# AIRZAI_NFC_READER_FLEX.net
KiCad netlist of a schematic drawn in Altium Designer
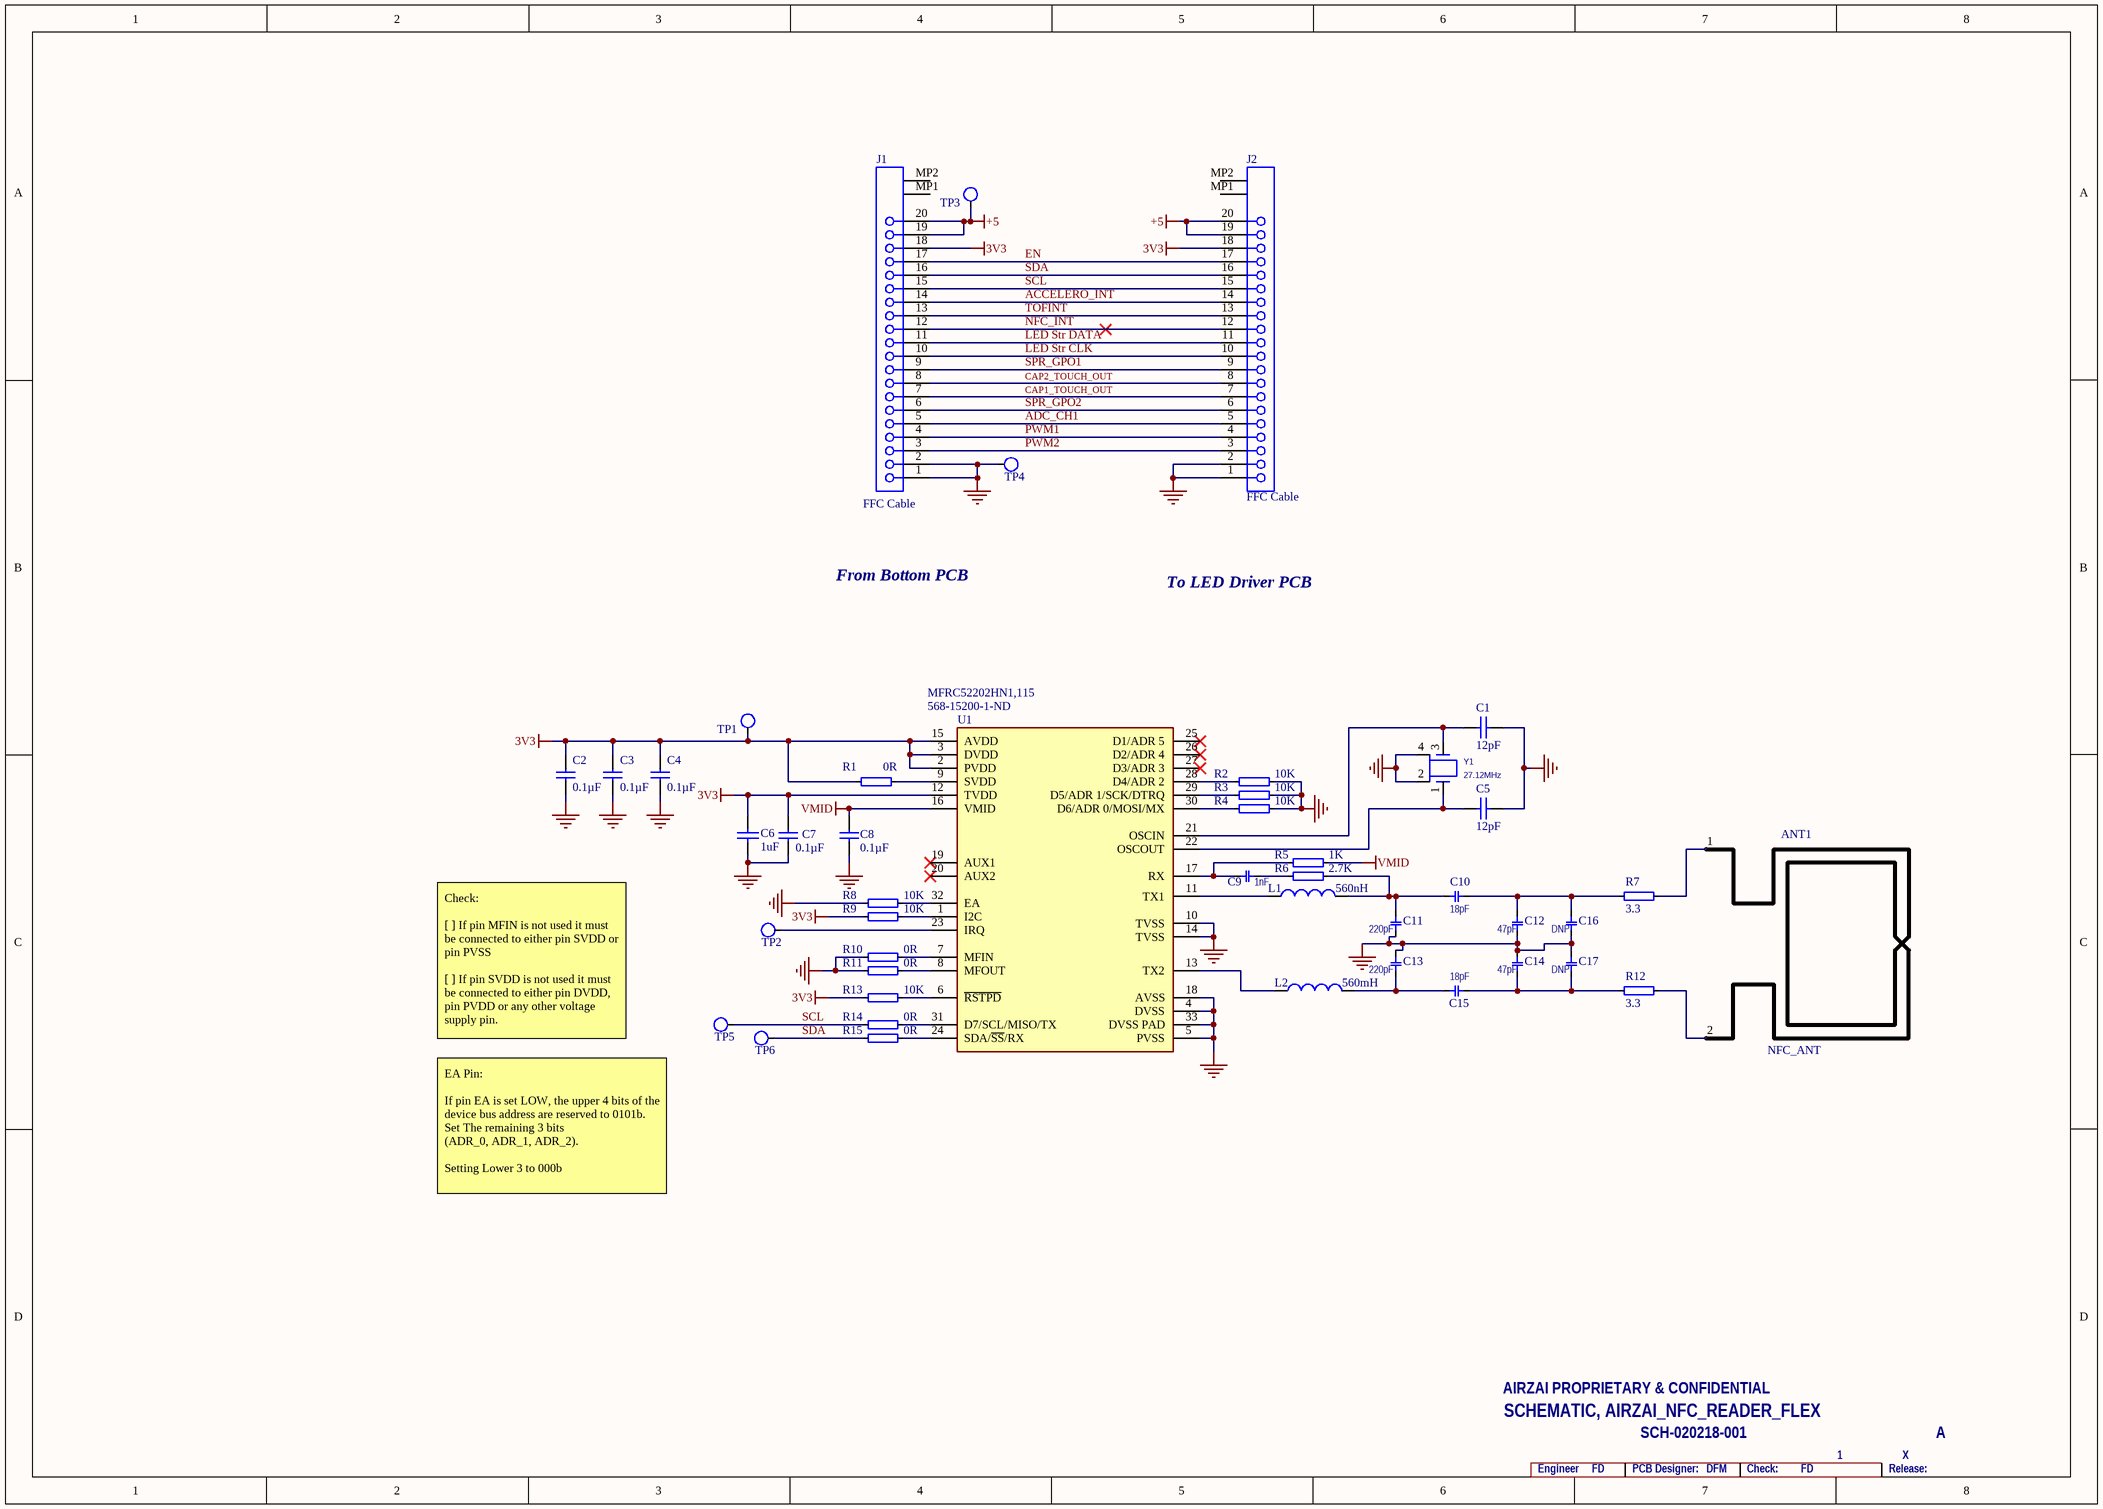
[diagram p0: AIRZAI_NFC_READER_FLEX.SchDoc]

(export (version "E")
  (design (tool "Eeschema 10.0.6"))
  (components
    (comp (ref "ANT1")
      (value "NFC_ANT")
      (footprint "ANTENNA-NFC-60MMX30MM")
      (libsource (lib "AIRZAI_LED_SENSE_FLEX_REVA") (part "NFC_ANT"))
    )
    (comp (ref "C1")
      (value "12pF")
      (footprint "0402CAP")
      (description "CAP CER 12PF 50V C0G/NP0 0402")
      (fields
        (field (name "MANUFACTURER") "KEMET")
        (field (name "MANUFACTURER PART NUMBER") "C0402C120J5GACTU")
      )
      (libsource (lib "AIRZAI_LED_SENSE_FLEX_REVA") (part "CAP"))
    )
    (comp (ref "C2")
      (value "0.1µF")
      (footprint "0402CAP")
      (description "Capacitor, X7R, ±10%")
      (fields (field (name "MANUFACTURER") "TDK") (field (name "MANUFACTURER PART NUMBER") "C1005X7R1C104K"))
      (libsource (lib "Nordic Passive DB") (part "CAP"))
    )
    (comp (ref "C3")
      (value "0.1µF")
      (footprint "0402CAP")
      (description "Capacitor, X7R, ±10%")
      (fields (field (name "MANUFACTURER") "TDK") (field (name "MANUFACTURER PART NUMBER") "C1005X7R1C104K"))
      (libsource (lib "Nordic Passive DB") (part "CAP"))
    )
    (comp (ref "C4")
      (value "0.1µF")
      (footprint "0402CAP")
      (description "Capacitor, X7R, ±10%")
      (fields (field (name "MANUFACTURER") "TDK") (field (name "MANUFACTURER PART NUMBER") "C1005X7R1C104K"))
      (libsource (lib "Nordic Passive DB") (part "CAP"))
    )
    (comp (ref "C5")
      (value "12pF")
      (footprint "0402CAP")
      (description "CAP CER 12PF 50V C0G/NP0 0402")
      (fields
        (field (name "MANUFACTURER") "KEMET")
        (field (name "MANUFACTURER PART NUMBER") "C0402C120J5GACTU")
      )
      (libsource (lib "AIRZAI_LED_SENSE_FLEX_REVA") (part "CAP"))
    )
    (comp (ref "C6")
      (value "1uF")
      (footprint "CAPC0402(1005)60_M")
      (description "CAP 1uF 16V ±10% 0402 (1005 Metric) Thickness 0.6mm SMD")
      (fields
        (field (name "MANUFACTURER") "Taiyo Yuden")
        (field (name "MANUFACTURER PART NUMBER") "EMK105BJ105KV-F")
      )
      (libsource (lib "AIRZAI_LED_SENSE_FLEX_REVA") (part "CAP"))
    )
    (comp (ref "C7")
      (value "0.1µF")
      (footprint "0402CAP")
      (description "Capacitor, X7R, ±10%")
      (fields (field (name "MANUFACTURER") "TDK") (field (name "MANUFACTURER PART NUMBER") "C1005X7R1C104K"))
      (libsource (lib "Nordic Passive DB") (part "CAP"))
    )
    (comp (ref "C8")
      (value "0.1µF")
      (footprint "0402CAP")
      (description "Capacitor, X7R, ±10%")
      (fields (field (name "MANUFACTURER") "TDK") (field (name "MANUFACTURER PART NUMBER") "C1005X7R1C104K"))
      (libsource (lib "Nordic Passive DB") (part "CAP"))
    )
    (comp (ref "C9")
      (value "1nF")
      (footprint "0402CAP")
      (description "CAP CER 1000PF 50V C0G/NP0 0402")
      (fields
        (field (name "MANUFACTURER") "Murata")
        (field (name "MANUFACTURER PART NUMBER") "GRM1555C1H102FA01D")
      )
      (libsource (lib "LID2131_PN7462AU V2") (part "56p"))
    )
    (comp (ref "C10")
      (value "18pF")
      (footprint "0402CAP")
      (description "CAP CER 18PF 50V NP0 0402")
      (fields
        (field (name "MANUFACTURER") "Kyocera AVX")
        (field (name "MANUFACTURER PART NUMBER") "04025U180FAT2A")
      )
      (libsource (lib "LID2131_PN7462AU V2") (part "56p"))
    )
    (comp (ref "C11")
      (value "220pF")
      (footprint "0402CAP")
      (description "CAP CER 220PF 50V NPO 0402")
      (fields
        (field (name "MANUFACTURER") "Yageo")
        (field (name "MANUFACTURER PART NUMBER") "CC0402FRNPO9BN221")
      )
      (libsource (lib "LID2131_PN7462AU V2") (part "56p"))
    )
    (comp (ref "C12")
      (value "47pF")
      (footprint "0402CAP")
      (description "CAP CER 47PF 50V C0G/NP0 0402")
      (fields
        (field (name "MANUFACTURER") "Murata")
        (field (name "MANUFACTURER PART NUMBER") "GJM1555C1H470FB01D")
      )
      (libsource (lib "LID2131_PN7462AU V2") (part "56p"))
    )
    (comp (ref "C13")
      (value "220pF")
      (footprint "0402CAP")
      (description "CAP CER 220PF 50V NPO 0402")
      (fields
        (field (name "MANUFACTURER") "Yageo")
        (field (name "MANUFACTURER PART NUMBER") "CC0402FRNPO9BN221")
      )
      (libsource (lib "LID2131_PN7462AU V2") (part "56p"))
    )
    (comp (ref "C14")
      (value "47pF")
      (footprint "0402CAP")
      (description "CAP CER 47PF 50V C0G/NP0 0402")
      (fields
        (field (name "MANUFACTURER") "Murata")
        (field (name "MANUFACTURER PART NUMBER") "GJM1555C1H470FB01D")
      )
      (libsource (lib "LID2131_PN7462AU V2") (part "56p"))
    )
    (comp (ref "C15")
      (value "18pF")
      (footprint "0402CAP")
      (description "CAP CER 18PF 50V NP0 0402")
      (fields
        (field (name "MANUFACTURER") "Kyocera AVX")
        (field (name "MANUFACTURER PART NUMBER") "04025U180FAT2A")
      )
      (libsource (lib "LID2131_PN7462AU V2") (part "56p"))
    )
    (comp (ref "C16")
      (value "DNP")
      (footprint "0402CAP")
      (libsource (lib "LID2131_PN7462AU V2") (part "56p"))
    )
    (comp (ref "C17")
      (value "DNP")
      (footprint "0402CAP")
      (libsource (lib "LID2131_PN7462AU V2") (part "56p"))
    )
    (comp (ref "J1")
      (value "FFC Cable")
      (footprint "FFC_Pads_MBD")
      (description "Cable")
      (libsource (lib "AIRZAI_LID_BD_REVA") (part "XF2M-2015-1A-R100"))
    )
    (comp (ref "J2")
      (value "FFC Cable")
      (footprint "FFC_Pads_LID")
      (description "Cable")
      (libsource (lib "AIRZAI_LID_BD_REVA") (part "XF2M-2015-1A-R100"))
    )
    (comp (ref "L1")
      (value "560nH")
      (footprint "0603CAP")
      (description "FIXED IND 560NH 100MA 1.05 OHM")
      (fields
        (field (name "MANUFACTURER") "TDK")
        (field (name "MANUFACTURER PART NUMBER") "MLF1608DR56JTD25")
      )
      (libsource (lib "Miscellaneous Devices") (part "Inductor"))
    )
    (comp (ref "L2")
      (value "560mH")
      (footprint "0603CAP")
      (description "FIXED IND 560NH 100MA 1.05 OHM")
      (fields
        (field (name "MANUFACTURER") "TDK")
        (field (name "MANUFACTURER PART NUMBER") "MLF1608DR56JTD25")
      )
      (libsource (lib "Miscellaneous Devices") (part "Inductor"))
    )
    (comp (ref "R1")
      (value "0R")
      (footprint "0402")
      (description "Resistor, ±1%, 0.063W")
      (fields
        (field (name "MANUFACTURER") "Panasonic")
        (field (name "MANUFACTURER PART NUMBER") "ERJ-2GE0R00X")
      )
      (libsource (lib "Nordic Passive DB") (part "RES_1"))
    )
    (comp (ref "R2")
      (value "10K")
      (footprint "0402")
      (description "Resistor 10K, ±1%, 0.063W")
      (fields
        (field (name "MANUFACTURER") "Vishay Dale")
        (field (name "MANUFACTURER PART NUMBER") "CRCW040210K0JNED")
      )
      (libsource (lib "Nordic Passive DB") (part "RES_1"))
    )
    (comp (ref "R3")
      (value "10K")
      (footprint "0402")
      (description "Resistor 10K, ±1%, 0.063W")
      (fields
        (field (name "MANUFACTURER") "Vishay Dale")
        (field (name "MANUFACTURER PART NUMBER") "CRCW040210K0JNED")
      )
      (libsource (lib "Nordic Passive DB") (part "RES_1"))
    )
    (comp (ref "R4")
      (value "10K")
      (footprint "0402")
      (description "Resistor 10K, ±1%, 0.063W")
      (fields
        (field (name "MANUFACTURER") "Vishay Dale")
        (field (name "MANUFACTURER PART NUMBER") "CRCW040210K0JNED")
      )
      (libsource (lib "Nordic Passive DB") (part "RES_1"))
    )
    (comp (ref "R5")
      (value "1K")
      (footprint "0402")
      (description "RES SMD 1K OHM 1% 1/16W 0402")
      (fields
        (field (name "MANUFACTURER") "Yageo")
        (field (name "MANUFACTURER PART NUMBER") "RC0402FR-071KL")
      )
      (libsource (lib "Nordic Passive DB") (part "RES_1"))
    )
    (comp (ref "R6")
      (value "2.7K")
      (footprint "0402")
      (description "RES SMD 2.7K OHM 1% 1/16W 0402")
      (fields
        (field (name "MANUFACTURER") "Yageo Phycomp")
        (field (name "MANUFACTURER PART NUMBER") "RC0402FR-072K7L")
      )
      (libsource (lib "Nordic Passive DB") (part "RES_1"))
    )
    (comp (ref "R7")
      (value "3.3")
      (footprint "0603")
      (description "RES SMD 3.3 OHM 1% 1/10W 0603")
      (fields
        (field (name "MANUFACTURER") "Yageo")
        (field (name "MANUFACTURER PART NUMBER") "AC0603FR-073R3L")
      )
      (libsource (lib "Nordic Passive DB") (part "RES_1"))
    )
    (comp (ref "R8")
      (value "10K")
      (footprint "0402")
      (description "Resistor 10K, ±1%, 0.063W")
      (fields
        (field (name "MANUFACTURER") "Vishay Dale")
        (field (name "MANUFACTURER PART NUMBER") "CRCW040210K0JNED")
      )
      (libsource (lib "Nordic Passive DB") (part "RES_1"))
    )
    (comp (ref "R9")
      (value "10K")
      (footprint "0402")
      (description "Resistor 10K, ±1%, 0.063W")
      (fields
        (field (name "MANUFACTURER") "Vishay Dale")
        (field (name "MANUFACTURER PART NUMBER") "CRCW040210K0JNED")
      )
      (libsource (lib "Nordic Passive DB") (part "RES_1"))
    )
    (comp (ref "R10")
      (value "0R")
      (footprint "0402")
      (description "Resistor, ±1%, 0.063W")
      (fields
        (field (name "MANUFACTURER") "Panasonic")
        (field (name "MANUFACTURER PART NUMBER") "ERJ-2GE0R00X")
      )
      (libsource (lib "Nordic Passive DB") (part "RES_1"))
    )
    (comp (ref "R11")
      (value "0R")
      (footprint "0402")
      (description "Resistor, ±1%, 0.063W")
      (fields
        (field (name "MANUFACTURER") "Panasonic")
        (field (name "MANUFACTURER PART NUMBER") "ERJ-2GE0R00X")
      )
      (libsource (lib "Nordic Passive DB") (part "RES_1"))
    )
    (comp (ref "R12")
      (value "3.3")
      (footprint "0603")
      (description "RES SMD 3.3 OHM 1% 1/10W 0603")
      (fields
        (field (name "MANUFACTURER") "Yageo")
        (field (name "MANUFACTURER PART NUMBER") "AC0603FR-073R3L")
      )
      (libsource (lib "Nordic Passive DB") (part "RES_1"))
    )
    (comp (ref "R13")
      (value "10K")
      (footprint "0402")
      (description "Resistor 10K, ±1%, 0.063W")
      (fields
        (field (name "MANUFACTURER") "Vishay Dale")
        (field (name "MANUFACTURER PART NUMBER") "CRCW040210K0JNED")
      )
      (libsource (lib "Nordic Passive DB") (part "RES_1"))
    )
    (comp (ref "R14")
      (value "0R")
      (footprint "0402")
      (description "Resistor, ±1%, 0.063W")
      (fields
        (field (name "MANUFACTURER") "Panasonic")
        (field (name "MANUFACTURER PART NUMBER") "ERJ-2GE0R00X")
      )
      (libsource (lib "Nordic Passive DB") (part "RES_1"))
    )
    (comp (ref "R15")
      (value "0R")
      (footprint "0402")
      (description "Resistor, ±1%, 0.063W")
      (fields
        (field (name "MANUFACTURER") "Panasonic")
        (field (name "MANUFACTURER PART NUMBER") "ERJ-2GE0R00X")
      )
      (libsource (lib "Nordic Passive DB") (part "RES_1"))
    )
    (comp (ref "TP1")
      (value "WIREPT")
      (footprint "TP_0.9MM")
      (libsource (lib "AIRZAI_MBD_REVB") (part "WIREPT"))
    )
    (comp (ref "TP2")
      (value "WIREPT")
      (footprint "TP_0.9MM")
      (libsource (lib "AIRZAI_MBD_REVB") (part "WIREPT"))
    )
    (comp (ref "TP3")
      (value "WIREPT")
      (footprint "TP_0.9MM")
      (libsource (lib "AIRZAI_MBD_REVB") (part "WIREPT"))
    )
    (comp (ref "TP4")
      (value "WIREPT")
      (footprint "TP_0.9MM")
      (libsource (lib "AIRZAI_MBD_REVB") (part "WIREPT"))
    )
    (comp (ref "TP5")
      (value "WIREPT")
      (footprint "TP_0.9MM")
      (libsource (lib "AIRZAI_MBD_REVB") (part "WIREPT"))
    )
    (comp (ref "TP6")
      (value "WIREPT")
      (footprint "TP_0.9MM")
      (libsource (lib "AIRZAI_MBD_REVB") (part "WIREPT"))
    )
    (comp (ref "U1")
      (value "MFRC52202HN1,115")
      (footprint "VFQFN-32-MFRC52202HN1,157")
      (description "IC RFID READER 13.56MHZ 32HVQFN")
      (fields
        (field (name "SUPPLIER PART NUMBER 1") "568-15200-1-ND")
        (field (name "MANUFACTURER") "NXP Semiconductors")
        (field (name "MANUFACTURER PART NUMBER") "MFRC52202HN1,115")
      )
      (libsource (lib "AIRZAI_LED_SENSE_FLEX_REVA") (part "MFRC52201HN1,157"))
    )
    (comp (ref "Y1")
      (value "27.12MHz")
      (footprint "XTAL_2016")
      (description "CRYSTAL 27.12MHZ 10PF SMD")
      (fields
        (field (name "MANUFACTURER") "ECS International")
        (field (name "MANUFACTURER PART NUMBER") "ECS-271.2-10-37-CKM-TR")
      )
      (libsource (lib "*") (part "ZTB_2"))
    )
  )
  (nets
    (net (code "1") (name "+5") (class "Default")
      (node (ref "J1") (pin "19") (pinfunction "19_19") (pintype "passive"))
      (node (ref "J1") (pin "20") (pinfunction "20_20") (pintype "passive"))
      (node (ref "J2") (pin "19") (pinfunction "19_19") (pintype "passive"))
      (node (ref "J2") (pin "20") (pinfunction "20_20") (pintype "passive"))
      (node (ref "TP3") (pin "1") (pinfunction "1_1") (pintype "passive"))
    )
    (net (code "2") (name "/ACCELERO_INT") (class "Default")
      (node (ref "J1") (pin "14") (pinfunction "14_14") (pintype "passive"))
      (node (ref "J2") (pin "14") (pinfunction "14_14") (pintype "passive"))
    )
    (net (code "3") (name "/ADC_CH1") (class "Default")
      (node (ref "J1") (pin "5") (pinfunction "5_5") (pintype "passive"))
      (node (ref "J2") (pin "5") (pinfunction "5_5") (pintype "passive"))
    )
    (net (code "4") (name "/CAP1_TOUCH_OUT") (class "Default")
      (node (ref "J1") (pin "7") (pinfunction "7_7") (pintype "passive"))
      (node (ref "J2") (pin "7") (pinfunction "7_7") (pintype "passive"))
    )
    (net (code "5") (name "/CAP2_TOUCH_OUT") (class "Default")
      (node (ref "J1") (pin "8") (pinfunction "8_8") (pintype "passive"))
      (node (ref "J2") (pin "8") (pinfunction "8_8") (pintype "passive"))
    )
    (net (code "6") (name "/EN") (class "Default")
      (node (ref "J1") (pin "17") (pinfunction "17_17") (pintype "passive"))
      (node (ref "J2") (pin "17") (pinfunction "17_17") (pintype "passive"))
    )
    (net (code "7") (name "/LED Str CLK") (class "Default")
      (node (ref "J1") (pin "10") (pinfunction "10_10") (pintype "passive"))
      (node (ref "J2") (pin "10") (pinfunction "10_10") (pintype "passive"))
    )
    (net (code "8") (name "/LED Str DATA") (class "Default")
      (node (ref "J1") (pin "11") (pinfunction "11_11") (pintype "passive"))
      (node (ref "J2") (pin "11") (pinfunction "11_11") (pintype "passive"))
    )
    (net (code "9") (name "/NFC_INT") (class "Default")
      (node (ref "J1") (pin "12") (pinfunction "12_12") (pintype "passive"))
      (node (ref "J2") (pin "12") (pinfunction "12_12") (pintype "passive"))
    )
    (net (code "10") (name "/PWM1") (class "Default")
      (node (ref "J1") (pin "4") (pinfunction "4_4") (pintype "passive"))
      (node (ref "J2") (pin "4") (pinfunction "4_4") (pintype "passive"))
    )
    (net (code "11") (name "/PWM2") (class "Default")
      (node (ref "J1") (pin "3") (pinfunction "3_3") (pintype "passive"))
      (node (ref "J2") (pin "3") (pinfunction "3_3") (pintype "passive"))
    )
    (net (code "12") (name "/SCL") (class "Default")
      (node (ref "J1") (pin "15") (pinfunction "15_15") (pintype "passive"))
      (node (ref "J2") (pin "15") (pinfunction "15_15") (pintype "passive"))
      (node (ref "R14") (pin "2") (pinfunction "2_2") (pintype "passive"))
      (node (ref "TP5") (pin "1") (pinfunction "1_1") (pintype "passive"))
    )
    (net (code "13") (name "/SDA") (class "Default")
      (node (ref "J1") (pin "16") (pinfunction "16_16") (pintype "passive"))
      (node (ref "J2") (pin "16") (pinfunction "16_16") (pintype "passive"))
      (node (ref "R15") (pin "2") (pinfunction "2_2") (pintype "passive"))
      (node (ref "TP6") (pin "1") (pinfunction "1_1") (pintype "passive"))
    )
    (net (code "14") (name "/SPR_GPO1") (class "Default")
      (node (ref "J1") (pin "9") (pinfunction "9_9") (pintype "passive"))
      (node (ref "J2") (pin "9") (pinfunction "9_9") (pintype "passive"))
    )
    (net (code "15") (name "/SPR_GPO2") (class "Default")
      (node (ref "J1") (pin "6") (pinfunction "6_6") (pintype "passive"))
      (node (ref "J2") (pin "6") (pinfunction "6_6") (pintype "passive"))
    )
    (net (code "16") (name "/TOFINT") (class "Default")
      (node (ref "J1") (pin "13") (pinfunction "13_13") (pintype "passive"))
      (node (ref "J2") (pin "13") (pinfunction "13_13") (pintype "passive"))
    )
    (net (code "17") (name "3V3") (class "Default")
      (node (ref "C2") (pin "1") (pinfunction "1_1") (pintype "passive"))
      (node (ref "C3") (pin "1") (pinfunction "1_1") (pintype "passive"))
      (node (ref "C4") (pin "1") (pinfunction "1_1") (pintype "passive"))
      (node (ref "C6") (pin "2") (pinfunction "2_2") (pintype "passive"))
      (node (ref "C7") (pin "1") (pinfunction "1_1") (pintype "passive"))
      (node (ref "J1") (pin "18") (pinfunction "18_18") (pintype "passive"))
      (node (ref "J2") (pin "18") (pinfunction "18_18") (pintype "passive"))
      (node (ref "R1") (pin "2") (pinfunction "2_2") (pintype "passive"))
      (node (ref "R13") (pin "2") (pinfunction "2_2") (pintype "passive"))
      (node (ref "R9") (pin "2") (pinfunction "2_2") (pintype "passive"))
      (node (ref "TP1") (pin "1") (pinfunction "1_1") (pintype "passive"))
      (node (ref "U1") (pin "12") (pinfunction "TVDD_12") (pintype "passive"))
      (node (ref "U1") (pin "15") (pinfunction "AVDD_15") (pintype "passive"))
      (node (ref "U1") (pin "2") (pinfunction "PVDD_2") (pintype "passive"))
      (node (ref "U1") (pin "3") (pinfunction "DVDD_3") (pintype "passive"))
    )
    (net (code "18") (name "GND") (class "Default")
      (node (ref "C1") (pin "1") (pinfunction "1_1") (pintype "passive"))
      (node (ref "C11") (pin "1") (pinfunction "1_1") (pintype "passive"))
      (node (ref "C12") (pin "1") (pinfunction "1_1") (pintype "passive"))
      (node (ref "C13") (pin "2") (pinfunction "2_2") (pintype "passive"))
      (node (ref "C14") (pin "2") (pinfunction "2_2") (pintype "passive"))
      (node (ref "C16") (pin "1") (pinfunction "1_1") (pintype "passive"))
      (node (ref "C17") (pin "2") (pinfunction "2_2") (pintype "passive"))
      (node (ref "C2") (pin "2") (pinfunction "2_2") (pintype "passive"))
      (node (ref "C3") (pin "2") (pinfunction "2_2") (pintype "passive"))
      (node (ref "C4") (pin "2") (pinfunction "2_2") (pintype "passive"))
      (node (ref "C5") (pin "1") (pinfunction "1_1") (pintype "passive"))
      (node (ref "C6") (pin "1") (pinfunction "1_1") (pintype "passive"))
      (node (ref "C7") (pin "2") (pinfunction "2_2") (pintype "passive"))
      (node (ref "C8") (pin "2") (pinfunction "2_2") (pintype "passive"))
      (node (ref "J1") (pin "1") (pinfunction "1_1") (pintype "passive"))
      (node (ref "J1") (pin "2") (pinfunction "2_2") (pintype "passive"))
      (node (ref "J2") (pin "1") (pinfunction "1_1") (pintype "passive"))
      (node (ref "J2") (pin "2") (pinfunction "2_2") (pintype "passive"))
      (node (ref "R10") (pin "2") (pinfunction "2_2") (pintype "passive"))
      (node (ref "R11") (pin "2") (pinfunction "2_2") (pintype "passive"))
      (node (ref "R2") (pin "1") (pinfunction "1_1") (pintype "passive"))
      (node (ref "R3") (pin "1") (pinfunction "1_1") (pintype "passive"))
      (node (ref "R4") (pin "1") (pinfunction "1_1") (pintype "passive"))
      (node (ref "R8") (pin "2") (pinfunction "2_2") (pintype "passive"))
      (node (ref "TP4") (pin "1") (pinfunction "1_1") (pintype "passive"))
      (node (ref "U1") (pin "10") (pinfunction "TVSS_10") (pintype "passive"))
      (node (ref "U1") (pin "14") (pinfunction "TVSS_14") (pintype "passive"))
      (node (ref "U1") (pin "18") (pinfunction "AVSS_18") (pintype "passive"))
      (node (ref "U1") (pin "33") (pinfunction "DVSS_PAD_33") (pintype "passive"))
      (node (ref "U1") (pin "4") (pinfunction "DVSS_4") (pintype "passive"))
      (node (ref "U1") (pin "5") (pinfunction "PVSS_5") (pintype "passive"))
      (node (ref "Y1") (pin "2") (pinfunction "2_2") (pintype "passive"))
      (node (ref "Y1") (pin "4") (pinfunction "4_4") (pintype "passive"))
    )
    (net (code "19") (name "Net-(ANT1-Pad1)") (class "Default")
      (node (ref "ANT1") (pin "1") (pinfunction "1_1") (pintype "passive"))
      (node (ref "R7") (pin "1") (pinfunction "1_1") (pintype "passive"))
    )
    (net (code "20") (name "Net-(ANT1-Pad2)") (class "Default")
      (node (ref "ANT1") (pin "2") (pinfunction "2_2") (pintype "passive"))
      (node (ref "R12") (pin "1") (pinfunction "1_1") (pintype "passive"))
    )
    (net (code "21") (name "Net-(C9-Pad1)") (class "Default")
      (node (ref "C9") (pin "1") (pinfunction "1_1") (pintype "passive"))
      (node (ref "R6") (pin "2") (pinfunction "2_2") (pintype "passive"))
    )
    (net (code "22") (name "Net-(C10-Pad1)") (class "Default")
      (node (ref "C10") (pin "1") (pinfunction "1_1") (pintype "passive"))
      (node (ref "C12") (pin "2") (pinfunction "2_2") (pintype "passive"))
      (node (ref "C16") (pin "2") (pinfunction "2_2") (pintype "passive"))
      (node (ref "R7") (pin "2") (pinfunction "2_2") (pintype "passive"))
    )
    (net (code "23") (name "Net-(C10-Pad2)") (class "Default")
      (node (ref "C10") (pin "2") (pinfunction "2_2") (pintype "passive"))
      (node (ref "C11") (pin "2") (pinfunction "2_2") (pintype "passive"))
      (node (ref "L1") (pin "2") (pinfunction "2_2") (pintype "passive"))
      (node (ref "R6") (pin "1") (pinfunction "1_1") (pintype "passive"))
    )
    (net (code "24") (name "Net-(C13-Pad1)") (class "Default")
      (node (ref "C13") (pin "1") (pinfunction "1_1") (pintype "passive"))
      (node (ref "C15") (pin "2") (pinfunction "2_2") (pintype "passive"))
      (node (ref "L2") (pin "2") (pinfunction "2_2") (pintype "passive"))
    )
    (net (code "25") (name "Net-(C14-Pad1)") (class "Default")
      (node (ref "C14") (pin "1") (pinfunction "1_1") (pintype "passive"))
      (node (ref "C15") (pin "1") (pinfunction "1_1") (pintype "passive"))
      (node (ref "C17") (pin "1") (pinfunction "1_1") (pintype "passive"))
      (node (ref "R12") (pin "2") (pinfunction "2_2") (pintype "passive"))
    )
    (net (code "26") (name "Net-(U1-D4{slash}ADR_2)") (class "Default")
      (node (ref "R2") (pin "2") (pinfunction "2_2") (pintype "passive"))
      (node (ref "U1") (pin "28") (pinfunction "D4/ADR_2_28") (pintype "passive"))
    )
    (net (code "27") (name "Net-(U1-D5{slash}ADR_1{slash}SCK{slash}DTRQ)") (class "Default")
      (node (ref "R3") (pin "2") (pinfunction "2_2") (pintype "passive"))
      (node (ref "U1") (pin "29") (pinfunction "D5/ADR_1/SCK/DTRQ_29") (pintype "passive"))
    )
    (net (code "28") (name "Net-(U1-D6{slash}ADR_0{slash}MOSI{slash}MX)") (class "Default")
      (node (ref "R4") (pin "2") (pinfunction "2_2") (pintype "passive"))
      (node (ref "U1") (pin "30") (pinfunction "D6/ADR_0/MOSI/MX_30") (pintype "passive"))
    )
    (net (code "29") (name "Net-(U1-D7{slash}SCL{slash}MISO{slash}TX)") (class "Default")
      (node (ref "R14") (pin "1") (pinfunction "1_1") (pintype "passive"))
      (node (ref "U1") (pin "31") (pinfunction "D7/SCL/MISO/TX_31") (pintype "passive"))
    )
    (net (code "30") (name "Net-(U1-EA)") (class "Default")
      (node (ref "R8") (pin "1") (pinfunction "1_1") (pintype "passive"))
      (node (ref "U1") (pin "32") (pinfunction "EA_32") (pintype "passive"))
    )
    (net (code "31") (name "Net-(U1-I2C)") (class "Default")
      (node (ref "R9") (pin "1") (pinfunction "1_1") (pintype "passive"))
      (node (ref "U1") (pin "1") (pinfunction "I2C_1") (pintype "passive"))
    )
    (net (code "32") (name "Net-(U1-IRQ)") (class "Default")
      (node (ref "TP2") (pin "1") (pinfunction "1_1") (pintype "passive"))
      (node (ref "U1") (pin "23") (pinfunction "IRQ_23") (pintype "passive"))
    )
    (net (code "33") (name "Net-(U1-MFIN)") (class "Default")
      (node (ref "R10") (pin "1") (pinfunction "1_1") (pintype "passive"))
      (node (ref "U1") (pin "7") (pinfunction "MFIN_7") (pintype "passive"))
    )
    (net (code "34") (name "Net-(U1-MFOUT)") (class "Default")
      (node (ref "R11") (pin "1") (pinfunction "1_1") (pintype "passive"))
      (node (ref "U1") (pin "8") (pinfunction "MFOUT_8") (pintype "passive"))
    )
    (net (code "35") (name "Net-(U1-OSCIN)") (class "Default")
      (node (ref "C1") (pin "2") (pinfunction "2_2") (pintype "passive"))
      (node (ref "U1") (pin "21") (pinfunction "OSCIN_21") (pintype "passive"))
      (node (ref "Y1") (pin "3") (pinfunction "3_3") (pintype "passive"))
    )
    (net (code "36") (name "Net-(U1-OSCOUT)") (class "Default")
      (node (ref "C5") (pin "2") (pinfunction "2_2") (pintype "passive"))
      (node (ref "U1") (pin "22") (pinfunction "OSCOUT_22") (pintype "passive"))
      (node (ref "Y1") (pin "1") (pinfunction "1_1") (pintype "passive"))
    )
    (net (code "37") (name "Net-(U1-RX)") (class "Default")
      (node (ref "C9") (pin "2") (pinfunction "2_2") (pintype "passive"))
      (node (ref "R5") (pin "2") (pinfunction "2_2") (pintype "passive"))
      (node (ref "U1") (pin "17") (pinfunction "RX_17") (pintype "passive"))
    )
    (net (code "38") (name "Net-(U1-SDA{slash}~{SS}{slash}RX)") (class "Default")
      (node (ref "R15") (pin "1") (pinfunction "1_1") (pintype "passive"))
      (node (ref "U1") (pin "24") (pinfunction "SDA/~{SS}/RX_24") (pintype "passive"))
    )
    (net (code "39") (name "Net-(U1-SVDD)") (class "Default")
      (node (ref "R1") (pin "1") (pinfunction "1_1") (pintype "passive"))
      (node (ref "U1") (pin "9") (pinfunction "SVDD_9") (pintype "passive"))
    )
    (net (code "40") (name "Net-(U1-TX1)") (class "Default")
      (node (ref "L1") (pin "1") (pinfunction "1_1") (pintype "passive"))
      (node (ref "U1") (pin "11") (pinfunction "TX1_11") (pintype "passive"))
    )
    (net (code "41") (name "Net-(U1-TX2)") (class "Default")
      (node (ref "L2") (pin "1") (pinfunction "1_1") (pintype "passive"))
      (node (ref "U1") (pin "13") (pinfunction "TX2_13") (pintype "passive"))
    )
    (net (code "42") (name "Net-(U1-~{RSTPD})") (class "Default")
      (node (ref "R13") (pin "1") (pinfunction "1_1") (pintype "passive"))
      (node (ref "U1") (pin "6") (pinfunction "~{RSTPD}_6") (pintype "passive"))
    )
    (net (code "43") (name "VMID") (class "Default")
      (node (ref "C8") (pin "1") (pinfunction "1_1") (pintype "passive"))
      (node (ref "R5") (pin "1") (pinfunction "1_1") (pintype "passive"))
      (node (ref "U1") (pin "16") (pinfunction "VMID_16") (pintype "passive"))
    )
    (net (code "44") (name "unconnected-(J1-PadMP1)") (class "Default")
      (node (ref "J1") (pin "MP1") (pinfunction "MP1_MP1") (pintype "passive"))
    )
    (net (code "45") (name "unconnected-(J1-PadMP2)") (class "Default")
      (node (ref "J1") (pin "MP2") (pinfunction "MP2_MP2") (pintype "passive"))
    )
    (net (code "46") (name "unconnected-(J2-PadMP1)") (class "Default")
      (node (ref "J2") (pin "MP1") (pinfunction "MP1_MP1") (pintype "passive"))
    )
    (net (code "47") (name "unconnected-(J2-PadMP2)") (class "Default")
      (node (ref "J2") (pin "MP2") (pinfunction "MP2_MP2") (pintype "passive"))
    )
    (net (code "48") (name "unconnected-(U1-AUX1-Pad19)") (class "Default")
      (node (ref "U1") (pin "19") (pinfunction "AUX1_19") (pintype "passive+no_connect"))
    )
    (net (code "49") (name "unconnected-(U1-AUX2-Pad20)") (class "Default")
      (node (ref "U1") (pin "20") (pinfunction "AUX2_20") (pintype "passive+no_connect"))
    )
    (net (code "50") (name "unconnected-(U1-D1{slash}ADR_5-Pad25)") (class "Default")
      (node (ref "U1") (pin "25") (pinfunction "D1/ADR_5_25") (pintype "passive+no_connect"))
    )
    (net (code "51") (name "unconnected-(U1-D2{slash}ADR_4-Pad26)") (class "Default")
      (node (ref "U1") (pin "26") (pinfunction "D2/ADR_4_26") (pintype "passive+no_connect"))
    )
    (net (code "52") (name "unconnected-(U1-D3{slash}ADR_3-Pad27)") (class "Default")
      (node (ref "U1") (pin "27") (pinfunction "D3/ADR_3_27") (pintype "passive+no_connect"))
    )
  )
)
